# Arduino_and_PMOD_Connectors.net
KiCad netlist of a schematic drawn in Altium Designer
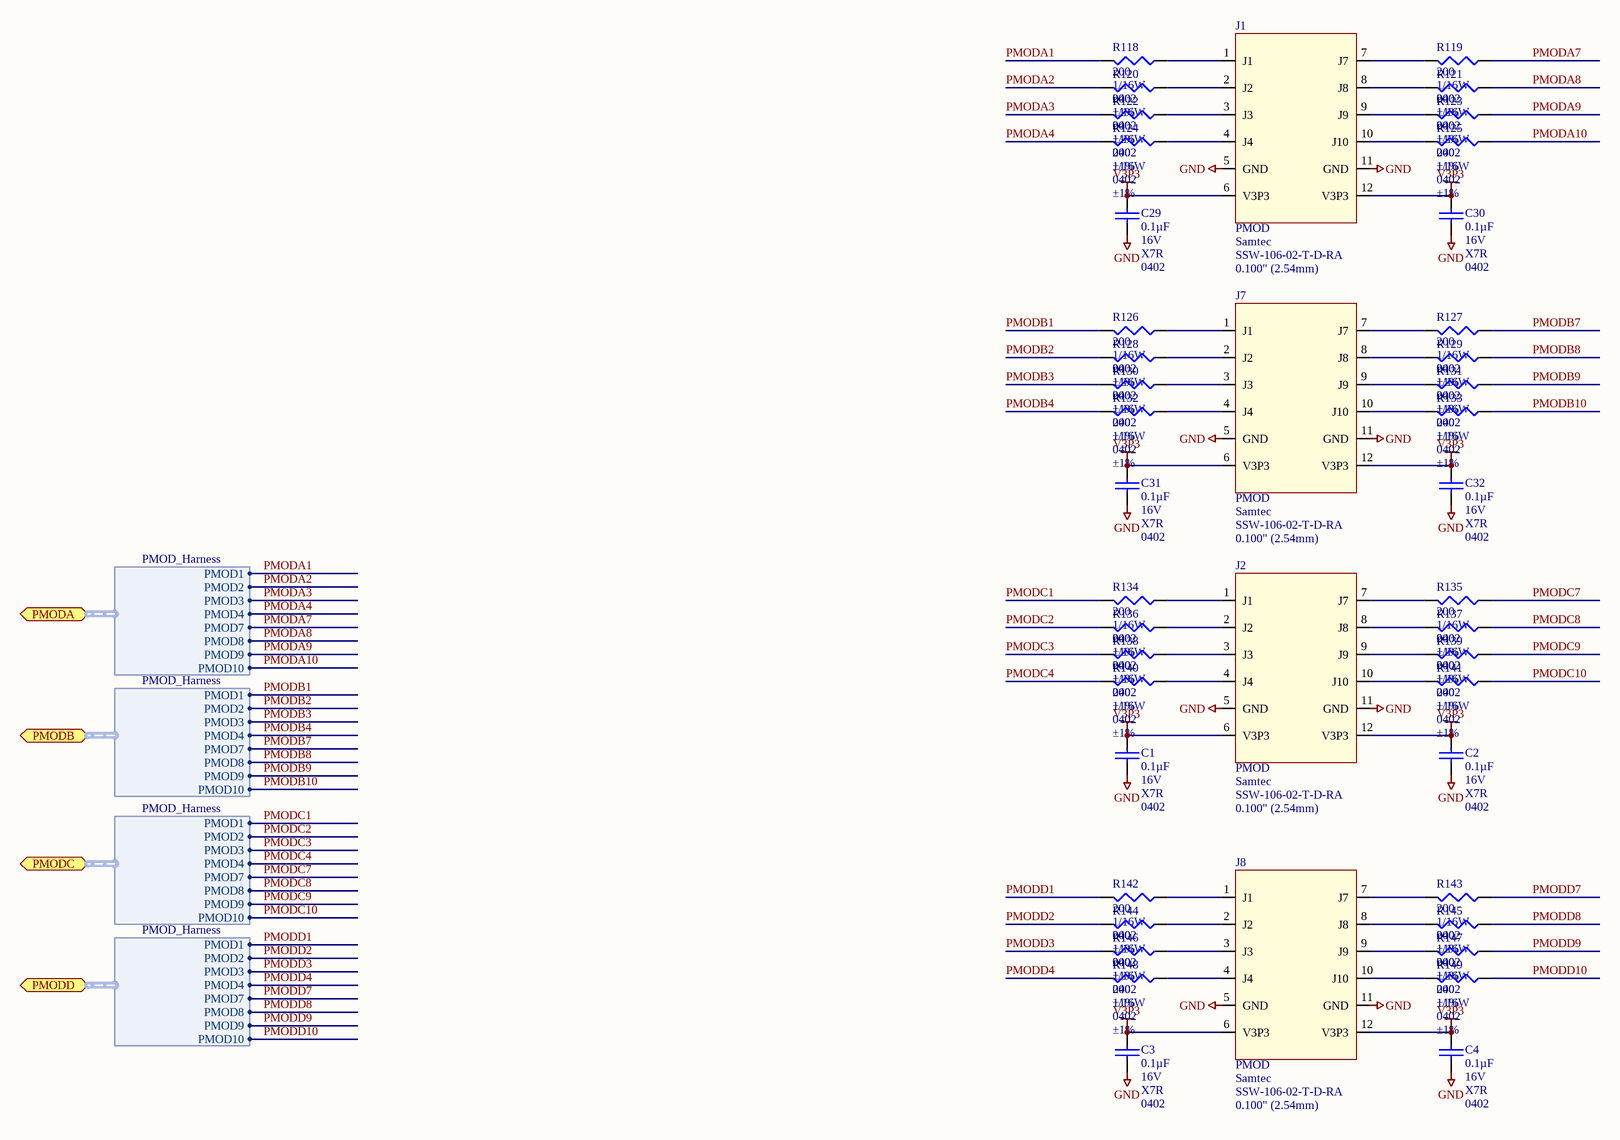
[diagram p0: Arduino and PMOD Connectors.SchDoc]

(export (version "E")
  (design (tool "Eeschema 10.0.6"))
  (components
    (comp (ref "C1")
      (value "0.1uF")
      (footprint "C_0402")
      (description "CAP CER .10UF 16V X7R 0402")
      (fields
        (field (name "MANUFACTURER") "Murata Electronics North America")
        (field (name "MANUFACTURER PART NUMBER") "GRM155R71C104KA88J")
        (field (name "CAPACITANCE") "0.1µF")
        (field (name "VOLTAGE - RATED") "16V")
        (field (name "TEMPERATURE COEFFICIENT") "X7R")
        (field (name "PACKAGE / CASE") "0402")
      )
      (libsource (lib "Main LibraryX") (part "C_0402_0.1UF_16V"))
    )
    (comp (ref "C2")
      (value "0.1uF")
      (footprint "C_0402")
      (description "CAP CER .10UF 16V X7R 0402")
      (fields
        (field (name "MANUFACTURER") "Murata Electronics North America")
        (field (name "MANUFACTURER PART NUMBER") "GRM155R71C104KA88J")
        (field (name "CAPACITANCE") "0.1µF")
        (field (name "VOLTAGE - RATED") "16V")
        (field (name "TEMPERATURE COEFFICIENT") "X7R")
        (field (name "PACKAGE / CASE") "0402")
      )
      (libsource (lib "Main LibraryX") (part "C_0402_0.1UF_16V"))
    )
    (comp (ref "C3")
      (value "0.1uF")
      (footprint "C_0402")
      (description "CAP CER .10UF 16V X7R 0402")
      (fields
        (field (name "MANUFACTURER") "Murata Electronics North America")
        (field (name "MANUFACTURER PART NUMBER") "GRM155R71C104KA88J")
        (field (name "CAPACITANCE") "0.1µF")
        (field (name "VOLTAGE - RATED") "16V")
        (field (name "TEMPERATURE COEFFICIENT") "X7R")
        (field (name "PACKAGE / CASE") "0402")
      )
      (libsource (lib "Main LibraryX") (part "C_0402_0.1UF_16V"))
    )
    (comp (ref "C4")
      (value "0.1uF")
      (footprint "C_0402")
      (description "CAP CER .10UF 16V X7R 0402")
      (fields
        (field (name "MANUFACTURER") "Murata Electronics North America")
        (field (name "MANUFACTURER PART NUMBER") "GRM155R71C104KA88J")
        (field (name "CAPACITANCE") "0.1µF")
        (field (name "VOLTAGE - RATED") "16V")
        (field (name "TEMPERATURE COEFFICIENT") "X7R")
        (field (name "PACKAGE / CASE") "0402")
      )
      (libsource (lib "Main LibraryX") (part "C_0402_0.1UF_16V"))
    )
    (comp (ref "C29")
      (value "0.1uF")
      (footprint "C_0402")
      (description "CAP CER .10UF 16V X7R 0402")
      (fields
        (field (name "MANUFACTURER") "Murata Electronics North America")
        (field (name "MANUFACTURER PART NUMBER") "GRM155R71C104KA88J")
        (field (name "CAPACITANCE") "0.1µF")
        (field (name "VOLTAGE - RATED") "16V")
        (field (name "TEMPERATURE COEFFICIENT") "X7R")
        (field (name "PACKAGE / CASE") "0402")
      )
      (libsource (lib "Main LibraryX") (part "C_0402_0.1UF_16V"))
    )
    (comp (ref "C30")
      (value "0.1uF")
      (footprint "C_0402")
      (description "CAP CER .10UF 16V X7R 0402")
      (fields
        (field (name "MANUFACTURER") "Murata Electronics North America")
        (field (name "MANUFACTURER PART NUMBER") "GRM155R71C104KA88J")
        (field (name "CAPACITANCE") "0.1µF")
        (field (name "VOLTAGE - RATED") "16V")
        (field (name "TEMPERATURE COEFFICIENT") "X7R")
        (field (name "PACKAGE / CASE") "0402")
      )
      (libsource (lib "Main LibraryX") (part "C_0402_0.1UF_16V"))
    )
    (comp (ref "C31")
      (value "0.1uF")
      (footprint "C_0402")
      (description "CAP CER .10UF 16V X7R 0402")
      (fields
        (field (name "MANUFACTURER") "Murata Electronics North America")
        (field (name "MANUFACTURER PART NUMBER") "GRM155R71C104KA88J")
        (field (name "CAPACITANCE") "0.1µF")
        (field (name "VOLTAGE - RATED") "16V")
        (field (name "TEMPERATURE COEFFICIENT") "X7R")
        (field (name "PACKAGE / CASE") "0402")
      )
      (libsource (lib "Main LibraryX") (part "C_0402_0.1UF_16V"))
    )
    (comp (ref "C32")
      (value "0.1uF")
      (footprint "C_0402")
      (description "CAP CER .10UF 16V X7R 0402")
      (fields
        (field (name "MANUFACTURER") "Murata Electronics North America")
        (field (name "MANUFACTURER PART NUMBER") "GRM155R71C104KA88J")
        (field (name "CAPACITANCE") "0.1µF")
        (field (name "VOLTAGE - RATED") "16V")
        (field (name "TEMPERATURE COEFFICIENT") "X7R")
        (field (name "PACKAGE / CASE") "0402")
      )
      (libsource (lib "Main LibraryX") (part "C_0402_0.1UF_16V"))
    )
    (comp (ref "J1")
      (value "PMOD")
      (footprint "PMOD")
      (description "CONN FEMALE 12POS DL .1\" R/A TIN")
      (fields
        (field (name "MANUFACTURER") "Samtec")
        (field (name "MANUFACTURER PART NUMBER") "SSW-106-02-T-D-RA")
        (field (name "PITCH") "0.100\" (2.54mm)")
      )
      (libsource (lib "Main LibraryX") (part "J_PMOD"))
    )
    (comp (ref "J2")
      (value "PMOD")
      (footprint "PMOD")
      (description "CONN FEMALE 12POS DL .1\" R/A TIN")
      (fields
        (field (name "MANUFACTURER") "Samtec")
        (field (name "MANUFACTURER PART NUMBER") "SSW-106-02-T-D-RA")
        (field (name "PITCH") "0.100\" (2.54mm)")
      )
      (libsource (lib "Main LibraryX") (part "J_PMOD"))
    )
    (comp (ref "J7")
      (value "PMOD")
      (footprint "PMOD")
      (description "CONN FEMALE 12POS DL .1\" R/A TIN")
      (fields
        (field (name "MANUFACTURER") "Samtec")
        (field (name "MANUFACTURER PART NUMBER") "SSW-106-02-T-D-RA")
        (field (name "PITCH") "0.100\" (2.54mm)")
      )
      (libsource (lib "Main LibraryX") (part "J_PMOD"))
    )
    (comp (ref "J8")
      (value "PMOD")
      (footprint "PMOD")
      (description "CONN FEMALE 12POS DL .1\" R/A TIN")
      (fields
        (field (name "MANUFACTURER") "Samtec")
        (field (name "MANUFACTURER PART NUMBER") "SSW-106-02-T-D-RA")
        (field (name "PITCH") "0.100\" (2.54mm)")
      )
      (libsource (lib "Main LibraryX") (part "J_PMOD"))
    )
    (comp (ref "R118")
      (value "R_0402_200")
      (footprint "R_0402")
      (description "RES 200 OHM 1/10W 1% 0402 SMD")
      (fields
        (field (name "MANUFACTURER") "Panasonic Electronic Components")
        (field (name "MANUFACTURER PART NUMBER") "ERJ-2RKF2000X")
        (field (name "RESISTANCE IN OHMS") "200")
        (field (name "POWER (WATTS)") "1/16W")
        (field (name "CASE") "0402")
        (field (name "TOLERANCE") "±1%")
      )
      (libsource (lib "Main LibraryX") (part "R_0402_200"))
    )
    (comp (ref "R119")
      (value "R_0402_200")
      (footprint "R_0402")
      (description "RES 200 OHM 1/10W 1% 0402 SMD")
      (fields
        (field (name "MANUFACTURER") "Panasonic Electronic Components")
        (field (name "MANUFACTURER PART NUMBER") "ERJ-2RKF2000X")
        (field (name "RESISTANCE IN OHMS") "200")
        (field (name "POWER (WATTS)") "1/16W")
        (field (name "CASE") "0402")
        (field (name "TOLERANCE") "±1%")
      )
      (libsource (lib "Main LibraryX") (part "R_0402_200"))
    )
    (comp (ref "R120")
      (value "R_0402_200")
      (footprint "R_0402")
      (description "RES 200 OHM 1/10W 1% 0402 SMD")
      (fields
        (field (name "MANUFACTURER") "Panasonic Electronic Components")
        (field (name "MANUFACTURER PART NUMBER") "ERJ-2RKF2000X")
        (field (name "RESISTANCE IN OHMS") "200")
        (field (name "POWER (WATTS)") "1/16W")
        (field (name "CASE") "0402")
        (field (name "TOLERANCE") "±1%")
      )
      (libsource (lib "Main LibraryX") (part "R_0402_200"))
    )
    (comp (ref "R121")
      (value "R_0402_200")
      (footprint "R_0402")
      (description "RES 200 OHM 1/10W 1% 0402 SMD")
      (fields
        (field (name "MANUFACTURER") "Panasonic Electronic Components")
        (field (name "MANUFACTURER PART NUMBER") "ERJ-2RKF2000X")
        (field (name "RESISTANCE IN OHMS") "200")
        (field (name "POWER (WATTS)") "1/16W")
        (field (name "CASE") "0402")
        (field (name "TOLERANCE") "±1%")
      )
      (libsource (lib "Main LibraryX") (part "R_0402_200"))
    )
    (comp (ref "R122")
      (value "R_0402_200")
      (footprint "R_0402")
      (description "RES 200 OHM 1/10W 1% 0402 SMD")
      (fields
        (field (name "MANUFACTURER") "Panasonic Electronic Components")
        (field (name "MANUFACTURER PART NUMBER") "ERJ-2RKF2000X")
        (field (name "RESISTANCE IN OHMS") "200")
        (field (name "POWER (WATTS)") "1/16W")
        (field (name "CASE") "0402")
        (field (name "TOLERANCE") "±1%")
      )
      (libsource (lib "Main LibraryX") (part "R_0402_200"))
    )
    (comp (ref "R123")
      (value "R_0402_200")
      (footprint "R_0402")
      (description "RES 200 OHM 1/10W 1% 0402 SMD")
      (fields
        (field (name "MANUFACTURER") "Panasonic Electronic Components")
        (field (name "MANUFACTURER PART NUMBER") "ERJ-2RKF2000X")
        (field (name "RESISTANCE IN OHMS") "200")
        (field (name "POWER (WATTS)") "1/16W")
        (field (name "CASE") "0402")
        (field (name "TOLERANCE") "±1%")
      )
      (libsource (lib "Main LibraryX") (part "R_0402_200"))
    )
    (comp (ref "R124")
      (value "R_0402_200")
      (footprint "R_0402")
      (description "RES 200 OHM 1/10W 1% 0402 SMD")
      (fields
        (field (name "MANUFACTURER") "Panasonic Electronic Components")
        (field (name "MANUFACTURER PART NUMBER") "ERJ-2RKF2000X")
        (field (name "RESISTANCE IN OHMS") "200")
        (field (name "POWER (WATTS)") "1/16W")
        (field (name "CASE") "0402")
        (field (name "TOLERANCE") "±1%")
      )
      (libsource (lib "Main LibraryX") (part "R_0402_200"))
    )
    (comp (ref "R125")
      (value "R_0402_200")
      (footprint "R_0402")
      (description "RES 200 OHM 1/10W 1% 0402 SMD")
      (fields
        (field (name "MANUFACTURER") "Panasonic Electronic Components")
        (field (name "MANUFACTURER PART NUMBER") "ERJ-2RKF2000X")
        (field (name "RESISTANCE IN OHMS") "200")
        (field (name "POWER (WATTS)") "1/16W")
        (field (name "CASE") "0402")
        (field (name "TOLERANCE") "±1%")
      )
      (libsource (lib "Main LibraryX") (part "R_0402_200"))
    )
    (comp (ref "R126")
      (value "R_0402_200")
      (footprint "R_0402")
      (description "RES 200 OHM 1/10W 1% 0402 SMD")
      (fields
        (field (name "MANUFACTURER") "Panasonic Electronic Components")
        (field (name "MANUFACTURER PART NUMBER") "ERJ-2RKF2000X")
        (field (name "RESISTANCE IN OHMS") "200")
        (field (name "POWER (WATTS)") "1/16W")
        (field (name "CASE") "0402")
        (field (name "TOLERANCE") "±1%")
      )
      (libsource (lib "Main LibraryX") (part "R_0402_200"))
    )
    (comp (ref "R127")
      (value "R_0402_200")
      (footprint "R_0402")
      (description "RES 200 OHM 1/10W 1% 0402 SMD")
      (fields
        (field (name "MANUFACTURER") "Panasonic Electronic Components")
        (field (name "MANUFACTURER PART NUMBER") "ERJ-2RKF2000X")
        (field (name "RESISTANCE IN OHMS") "200")
        (field (name "POWER (WATTS)") "1/16W")
        (field (name "CASE") "0402")
        (field (name "TOLERANCE") "±1%")
      )
      (libsource (lib "Main LibraryX") (part "R_0402_200"))
    )
    (comp (ref "R128")
      (value "R_0402_200")
      (footprint "R_0402")
      (description "RES 200 OHM 1/10W 1% 0402 SMD")
      (fields
        (field (name "MANUFACTURER") "Panasonic Electronic Components")
        (field (name "MANUFACTURER PART NUMBER") "ERJ-2RKF2000X")
        (field (name "RESISTANCE IN OHMS") "200")
        (field (name "POWER (WATTS)") "1/16W")
        (field (name "CASE") "0402")
        (field (name "TOLERANCE") "±1%")
      )
      (libsource (lib "Main LibraryX") (part "R_0402_200"))
    )
    (comp (ref "R129")
      (value "R_0402_200")
      (footprint "R_0402")
      (description "RES 200 OHM 1/10W 1% 0402 SMD")
      (fields
        (field (name "MANUFACTURER") "Panasonic Electronic Components")
        (field (name "MANUFACTURER PART NUMBER") "ERJ-2RKF2000X")
        (field (name "RESISTANCE IN OHMS") "200")
        (field (name "POWER (WATTS)") "1/16W")
        (field (name "CASE") "0402")
        (field (name "TOLERANCE") "±1%")
      )
      (libsource (lib "Main LibraryX") (part "R_0402_200"))
    )
    (comp (ref "R130")
      (value "R_0402_200")
      (footprint "R_0402")
      (description "RES 200 OHM 1/10W 1% 0402 SMD")
      (fields
        (field (name "MANUFACTURER") "Panasonic Electronic Components")
        (field (name "MANUFACTURER PART NUMBER") "ERJ-2RKF2000X")
        (field (name "RESISTANCE IN OHMS") "200")
        (field (name "POWER (WATTS)") "1/16W")
        (field (name "CASE") "0402")
        (field (name "TOLERANCE") "±1%")
      )
      (libsource (lib "Main LibraryX") (part "R_0402_200"))
    )
    (comp (ref "R131")
      (value "R_0402_200")
      (footprint "R_0402")
      (description "RES 200 OHM 1/10W 1% 0402 SMD")
      (fields
        (field (name "MANUFACTURER") "Panasonic Electronic Components")
        (field (name "MANUFACTURER PART NUMBER") "ERJ-2RKF2000X")
        (field (name "RESISTANCE IN OHMS") "200")
        (field (name "POWER (WATTS)") "1/16W")
        (field (name "CASE") "0402")
        (field (name "TOLERANCE") "±1%")
      )
      (libsource (lib "Main LibraryX") (part "R_0402_200"))
    )
    (comp (ref "R132")
      (value "R_0402_200")
      (footprint "R_0402")
      (description "RES 200 OHM 1/10W 1% 0402 SMD")
      (fields
        (field (name "MANUFACTURER") "Panasonic Electronic Components")
        (field (name "MANUFACTURER PART NUMBER") "ERJ-2RKF2000X")
        (field (name "RESISTANCE IN OHMS") "200")
        (field (name "POWER (WATTS)") "1/16W")
        (field (name "CASE") "0402")
        (field (name "TOLERANCE") "±1%")
      )
      (libsource (lib "Main LibraryX") (part "R_0402_200"))
    )
    (comp (ref "R133")
      (value "R_0402_200")
      (footprint "R_0402")
      (description "RES 200 OHM 1/10W 1% 0402 SMD")
      (fields
        (field (name "MANUFACTURER") "Panasonic Electronic Components")
        (field (name "MANUFACTURER PART NUMBER") "ERJ-2RKF2000X")
        (field (name "RESISTANCE IN OHMS") "200")
        (field (name "POWER (WATTS)") "1/16W")
        (field (name "CASE") "0402")
        (field (name "TOLERANCE") "±1%")
      )
      (libsource (lib "Main LibraryX") (part "R_0402_200"))
    )
    (comp (ref "R134")
      (value "R_0402_200")
      (footprint "R_0402")
      (description "RES 200 OHM 1/10W 1% 0402 SMD")
      (fields
        (field (name "MANUFACTURER") "Panasonic Electronic Components")
        (field (name "MANUFACTURER PART NUMBER") "ERJ-2RKF2000X")
        (field (name "RESISTANCE IN OHMS") "200")
        (field (name "POWER (WATTS)") "1/16W")
        (field (name "CASE") "0402")
        (field (name "TOLERANCE") "±1%")
      )
      (libsource (lib "Main LibraryX") (part "R_0402_200"))
    )
    (comp (ref "R135")
      (value "R_0402_200")
      (footprint "R_0402")
      (description "RES 200 OHM 1/10W 1% 0402 SMD")
      (fields
        (field (name "MANUFACTURER") "Panasonic Electronic Components")
        (field (name "MANUFACTURER PART NUMBER") "ERJ-2RKF2000X")
        (field (name "RESISTANCE IN OHMS") "200")
        (field (name "POWER (WATTS)") "1/16W")
        (field (name "CASE") "0402")
        (field (name "TOLERANCE") "±1%")
      )
      (libsource (lib "Main LibraryX") (part "R_0402_200"))
    )
    (comp (ref "R136")
      (value "R_0402_200")
      (footprint "R_0402")
      (description "RES 200 OHM 1/10W 1% 0402 SMD")
      (fields
        (field (name "MANUFACTURER") "Panasonic Electronic Components")
        (field (name "MANUFACTURER PART NUMBER") "ERJ-2RKF2000X")
        (field (name "RESISTANCE IN OHMS") "200")
        (field (name "POWER (WATTS)") "1/16W")
        (field (name "CASE") "0402")
        (field (name "TOLERANCE") "±1%")
      )
      (libsource (lib "Main LibraryX") (part "R_0402_200"))
    )
    (comp (ref "R137")
      (value "R_0402_200")
      (footprint "R_0402")
      (description "RES 200 OHM 1/10W 1% 0402 SMD")
      (fields
        (field (name "MANUFACTURER") "Panasonic Electronic Components")
        (field (name "MANUFACTURER PART NUMBER") "ERJ-2RKF2000X")
        (field (name "RESISTANCE IN OHMS") "200")
        (field (name "POWER (WATTS)") "1/16W")
        (field (name "CASE") "0402")
        (field (name "TOLERANCE") "±1%")
      )
      (libsource (lib "Main LibraryX") (part "R_0402_200"))
    )
    (comp (ref "R138")
      (value "R_0402_200")
      (footprint "R_0402")
      (description "RES 200 OHM 1/10W 1% 0402 SMD")
      (fields
        (field (name "MANUFACTURER") "Panasonic Electronic Components")
        (field (name "MANUFACTURER PART NUMBER") "ERJ-2RKF2000X")
        (field (name "RESISTANCE IN OHMS") "200")
        (field (name "POWER (WATTS)") "1/16W")
        (field (name "CASE") "0402")
        (field (name "TOLERANCE") "±1%")
      )
      (libsource (lib "Main LibraryX") (part "R_0402_200"))
    )
    (comp (ref "R139")
      (value "R_0402_200")
      (footprint "R_0402")
      (description "RES 200 OHM 1/10W 1% 0402 SMD")
      (fields
        (field (name "MANUFACTURER") "Panasonic Electronic Components")
        (field (name "MANUFACTURER PART NUMBER") "ERJ-2RKF2000X")
        (field (name "RESISTANCE IN OHMS") "200")
        (field (name "POWER (WATTS)") "1/16W")
        (field (name "CASE") "0402")
        (field (name "TOLERANCE") "±1%")
      )
      (libsource (lib "Main LibraryX") (part "R_0402_200"))
    )
    (comp (ref "R140")
      (value "R_0402_200")
      (footprint "R_0402")
      (description "RES 200 OHM 1/10W 1% 0402 SMD")
      (fields
        (field (name "MANUFACTURER") "Panasonic Electronic Components")
        (field (name "MANUFACTURER PART NUMBER") "ERJ-2RKF2000X")
        (field (name "RESISTANCE IN OHMS") "200")
        (field (name "POWER (WATTS)") "1/16W")
        (field (name "CASE") "0402")
        (field (name "TOLERANCE") "±1%")
      )
      (libsource (lib "Main LibraryX") (part "R_0402_200"))
    )
    (comp (ref "R141")
      (value "R_0402_200")
      (footprint "R_0402")
      (description "RES 200 OHM 1/10W 1% 0402 SMD")
      (fields
        (field (name "MANUFACTURER") "Panasonic Electronic Components")
        (field (name "MANUFACTURER PART NUMBER") "ERJ-2RKF2000X")
        (field (name "RESISTANCE IN OHMS") "200")
        (field (name "POWER (WATTS)") "1/16W")
        (field (name "CASE") "0402")
        (field (name "TOLERANCE") "±1%")
      )
      (libsource (lib "Main LibraryX") (part "R_0402_200"))
    )
    (comp (ref "R142")
      (value "R_0402_200")
      (footprint "R_0402")
      (description "RES 200 OHM 1/10W 1% 0402 SMD")
      (fields
        (field (name "MANUFACTURER") "Panasonic Electronic Components")
        (field (name "MANUFACTURER PART NUMBER") "ERJ-2RKF2000X")
        (field (name "RESISTANCE IN OHMS") "200")
        (field (name "POWER (WATTS)") "1/16W")
        (field (name "CASE") "0402")
        (field (name "TOLERANCE") "±1%")
      )
      (libsource (lib "Main LibraryX") (part "R_0402_200"))
    )
    (comp (ref "R143")
      (value "R_0402_200")
      (footprint "R_0402")
      (description "RES 200 OHM 1/10W 1% 0402 SMD")
      (fields
        (field (name "MANUFACTURER") "Panasonic Electronic Components")
        (field (name "MANUFACTURER PART NUMBER") "ERJ-2RKF2000X")
        (field (name "RESISTANCE IN OHMS") "200")
        (field (name "POWER (WATTS)") "1/16W")
        (field (name "CASE") "0402")
        (field (name "TOLERANCE") "±1%")
      )
      (libsource (lib "Main LibraryX") (part "R_0402_200"))
    )
    (comp (ref "R144")
      (value "R_0402_200")
      (footprint "R_0402")
      (description "RES 200 OHM 1/10W 1% 0402 SMD")
      (fields
        (field (name "MANUFACTURER") "Panasonic Electronic Components")
        (field (name "MANUFACTURER PART NUMBER") "ERJ-2RKF2000X")
        (field (name "RESISTANCE IN OHMS") "200")
        (field (name "POWER (WATTS)") "1/16W")
        (field (name "CASE") "0402")
        (field (name "TOLERANCE") "±1%")
      )
      (libsource (lib "Main LibraryX") (part "R_0402_200"))
    )
    (comp (ref "R145")
      (value "R_0402_200")
      (footprint "R_0402")
      (description "RES 200 OHM 1/10W 1% 0402 SMD")
      (fields
        (field (name "MANUFACTURER") "Panasonic Electronic Components")
        (field (name "MANUFACTURER PART NUMBER") "ERJ-2RKF2000X")
        (field (name "RESISTANCE IN OHMS") "200")
        (field (name "POWER (WATTS)") "1/16W")
        (field (name "CASE") "0402")
        (field (name "TOLERANCE") "±1%")
      )
      (libsource (lib "Main LibraryX") (part "R_0402_200"))
    )
    (comp (ref "R146")
      (value "R_0402_200")
      (footprint "R_0402")
      (description "RES 200 OHM 1/10W 1% 0402 SMD")
      (fields
        (field (name "MANUFACTURER") "Panasonic Electronic Components")
        (field (name "MANUFACTURER PART NUMBER") "ERJ-2RKF2000X")
        (field (name "RESISTANCE IN OHMS") "200")
        (field (name "POWER (WATTS)") "1/16W")
        (field (name "CASE") "0402")
        (field (name "TOLERANCE") "±1%")
      )
      (libsource (lib "Main LibraryX") (part "R_0402_200"))
    )
    (comp (ref "R147")
      (value "R_0402_200")
      (footprint "R_0402")
      (description "RES 200 OHM 1/10W 1% 0402 SMD")
      (fields
        (field (name "MANUFACTURER") "Panasonic Electronic Components")
        (field (name "MANUFACTURER PART NUMBER") "ERJ-2RKF2000X")
        (field (name "RESISTANCE IN OHMS") "200")
        (field (name "POWER (WATTS)") "1/16W")
        (field (name "CASE") "0402")
        (field (name "TOLERANCE") "±1%")
      )
      (libsource (lib "Main LibraryX") (part "R_0402_200"))
    )
    (comp (ref "R148")
      (value "R_0402_200")
      (footprint "R_0402")
      (description "RES 200 OHM 1/10W 1% 0402 SMD")
      (fields
        (field (name "MANUFACTURER") "Panasonic Electronic Components")
        (field (name "MANUFACTURER PART NUMBER") "ERJ-2RKF2000X")
        (field (name "RESISTANCE IN OHMS") "200")
        (field (name "POWER (WATTS)") "1/16W")
        (field (name "CASE") "0402")
        (field (name "TOLERANCE") "±1%")
      )
      (libsource (lib "Main LibraryX") (part "R_0402_200"))
    )
    (comp (ref "R149")
      (value "R_0402_200")
      (footprint "R_0402")
      (description "RES 200 OHM 1/10W 1% 0402 SMD")
      (fields
        (field (name "MANUFACTURER") "Panasonic Electronic Components")
        (field (name "MANUFACTURER PART NUMBER") "ERJ-2RKF2000X")
        (field (name "RESISTANCE IN OHMS") "200")
        (field (name "POWER (WATTS)") "1/16W")
        (field (name "CASE") "0402")
        (field (name "TOLERANCE") "±1%")
      )
      (libsource (lib "Main LibraryX") (part "R_0402_200"))
    )
  )
  (nets
    (net (code "2") (name "/PMODA1") (class "Default")
      (node (ref "R118") (pin "1") (pinfunction "1_1") (pintype "passive"))
    )
    (net (code "3") (name "/PMODA2") (class "Default")
      (node (ref "R120") (pin "1") (pinfunction "1_1") (pintype "passive"))
    )
    (net (code "4") (name "/PMODA3") (class "Default")
      (node (ref "R122") (pin "1") (pinfunction "1_1") (pintype "passive"))
    )
    (net (code "5") (name "/PMODA4") (class "Default")
      (node (ref "R124") (pin "1") (pinfunction "1_1") (pintype "passive"))
    )
    (net (code "6") (name "/PMODA7") (class "Default")
      (node (ref "R119") (pin "2") (pinfunction "2_2") (pintype "passive"))
    )
    (net (code "7") (name "/PMODA8") (class "Default")
      (node (ref "R121") (pin "2") (pinfunction "2_2") (pintype "passive"))
    )
    (net (code "8") (name "/PMODA9") (class "Default")
      (node (ref "R123") (pin "2") (pinfunction "2_2") (pintype "passive"))
    )
    (net (code "9") (name "/PMODA10") (class "Default")
      (node (ref "R125") (pin "2") (pinfunction "2_2") (pintype "passive"))
    )
    (net (code "10") (name "/PMODB1") (class "Default")
      (node (ref "R126") (pin "1") (pinfunction "1_1") (pintype "passive"))
    )
    (net (code "11") (name "/PMODB2") (class "Default")
      (node (ref "R128") (pin "1") (pinfunction "1_1") (pintype "passive"))
    )
    (net (code "12") (name "/PMODB3") (class "Default")
      (node (ref "R130") (pin "1") (pinfunction "1_1") (pintype "passive"))
    )
    (net (code "13") (name "/PMODB4") (class "Default")
      (node (ref "R132") (pin "1") (pinfunction "1_1") (pintype "passive"))
    )
    (net (code "14") (name "/PMODB7") (class "Default")
      (node (ref "R127") (pin "2") (pinfunction "2_2") (pintype "passive"))
    )
    (net (code "15") (name "/PMODB8") (class "Default")
      (node (ref "R129") (pin "2") (pinfunction "2_2") (pintype "passive"))
    )
    (net (code "16") (name "/PMODB9") (class "Default")
      (node (ref "R131") (pin "2") (pinfunction "2_2") (pintype "passive"))
    )
    (net (code "17") (name "/PMODB10") (class "Default")
      (node (ref "R133") (pin "2") (pinfunction "2_2") (pintype "passive"))
    )
    (net (code "18") (name "/PMODC1") (class "Default")
      (node (ref "R134") (pin "1") (pinfunction "1_1") (pintype "passive"))
    )
    (net (code "19") (name "/PMODC2") (class "Default")
      (node (ref "R136") (pin "1") (pinfunction "1_1") (pintype "passive"))
    )
    (net (code "20") (name "/PMODC3") (class "Default")
      (node (ref "R138") (pin "1") (pinfunction "1_1") (pintype "passive"))
    )
    (net (code "21") (name "/PMODC4") (class "Default")
      (node (ref "R140") (pin "1") (pinfunction "1_1") (pintype "passive"))
    )
    (net (code "22") (name "/PMODC7") (class "Default")
      (node (ref "R135") (pin "2") (pinfunction "2_2") (pintype "passive"))
    )
    (net (code "23") (name "/PMODC8") (class "Default")
      (node (ref "R137") (pin "2") (pinfunction "2_2") (pintype "passive"))
    )
    (net (code "24") (name "/PMODC9") (class "Default")
      (node (ref "R139") (pin "2") (pinfunction "2_2") (pintype "passive"))
    )
    (net (code "25") (name "/PMODC10") (class "Default")
      (node (ref "R141") (pin "2") (pinfunction "2_2") (pintype "passive"))
    )
    (net (code "26") (name "/PMODD1") (class "Default")
      (node (ref "R142") (pin "1") (pinfunction "1_1") (pintype "passive"))
    )
    (net (code "27") (name "/PMODD2") (class "Default")
      (node (ref "R144") (pin "1") (pinfunction "1_1") (pintype "passive"))
    )
    (net (code "28") (name "/PMODD3") (class "Default")
      (node (ref "R146") (pin "1") (pinfunction "1_1") (pintype "passive"))
    )
    (net (code "29") (name "/PMODD4") (class "Default")
      (node (ref "R148") (pin "1") (pinfunction "1_1") (pintype "passive"))
    )
    (net (code "30") (name "/PMODD7") (class "Default")
      (node (ref "R143") (pin "2") (pinfunction "2_2") (pintype "passive"))
    )
    (net (code "31") (name "/PMODD8") (class "Default")
      (node (ref "R145") (pin "2") (pinfunction "2_2") (pintype "passive"))
    )
    (net (code "32") (name "/PMODD9") (class "Default")
      (node (ref "R147") (pin "2") (pinfunction "2_2") (pintype "passive"))
    )
    (net (code "33") (name "/PMODD10") (class "Default")
      (node (ref "R149") (pin "2") (pinfunction "2_2") (pintype "passive"))
    )
    (net (code "35") (name "GND") (class "Default")
      (node (ref "C1") (pin "1") (pinfunction "1_1") (pintype "passive"))
      (node (ref "C2") (pin "1") (pinfunction "1_1") (pintype "passive"))
      (node (ref "C29") (pin "1") (pinfunction "1_1") (pintype "passive"))
      (node (ref "C3") (pin "1") (pinfunction "1_1") (pintype "passive"))
      (node (ref "C30") (pin "1") (pinfunction "1_1") (pintype "passive"))
      (node (ref "C31") (pin "1") (pinfunction "1_1") (pintype "passive"))
      (node (ref "C32") (pin "1") (pinfunction "1_1") (pintype "passive"))
      (node (ref "C4") (pin "1") (pinfunction "1_1") (pintype "passive"))
      (node (ref "J1") (pin "11") (pinfunction "GND_11") (pintype "passive"))
      (node (ref "J1") (pin "5") (pinfunction "GND_5") (pintype "passive"))
      (node (ref "J2") (pin "11") (pinfunction "GND_11") (pintype "passive"))
      (node (ref "J2") (pin "5") (pinfunction "GND_5") (pintype "passive"))
      (node (ref "J7") (pin "11") (pinfunction "GND_11") (pintype "passive"))
      (node (ref "J7") (pin "5") (pinfunction "GND_5") (pintype "passive"))
      (node (ref "J8") (pin "11") (pinfunction "GND_11") (pintype "passive"))
      (node (ref "J8") (pin "5") (pinfunction "GND_5") (pintype "passive"))
    )
    (net (code "36") (name "Net-(J1-J1)") (class "Default")
      (node (ref "J1") (pin "1") (pinfunction "J1_1") (pintype "passive"))
      (node (ref "R118") (pin "2") (pinfunction "2_2") (pintype "passive"))
    )
    (net (code "37") (name "Net-(J1-J2)") (class "Default")
      (node (ref "J1") (pin "2") (pinfunction "J2_2") (pintype "passive"))
      (node (ref "R120") (pin "2") (pinfunction "2_2") (pintype "passive"))
    )
    (net (code "38") (name "Net-(J1-J3)") (class "Default")
      (node (ref "J1") (pin "3") (pinfunction "J3_3") (pintype "passive"))
      (node (ref "R122") (pin "2") (pinfunction "2_2") (pintype "passive"))
    )
    (net (code "39") (name "Net-(J1-J4)") (class "Default")
      (node (ref "J1") (pin "4") (pinfunction "J4_4") (pintype "passive"))
      (node (ref "R124") (pin "2") (pinfunction "2_2") (pintype "passive"))
    )
    (net (code "40") (name "Net-(J1-J7)") (class "Default")
      (node (ref "J1") (pin "7") (pinfunction "J7_7") (pintype "passive"))
      (node (ref "R119") (pin "1") (pinfunction "1_1") (pintype "passive"))
    )
    (net (code "41") (name "Net-(J1-J8)") (class "Default")
      (node (ref "J1") (pin "8") (pinfunction "J8_8") (pintype "passive"))
      (node (ref "R121") (pin "1") (pinfunction "1_1") (pintype "passive"))
    )
    (net (code "42") (name "Net-(J1-J9)") (class "Default")
      (node (ref "J1") (pin "9") (pinfunction "J9_9") (pintype "passive"))
      (node (ref "R123") (pin "1") (pinfunction "1_1") (pintype "passive"))
    )
    (net (code "43") (name "Net-(J1-J10)") (class "Default")
      (node (ref "J1") (pin "10") (pinfunction "J10_10") (pintype "passive"))
      (node (ref "R125") (pin "1") (pinfunction "1_1") (pintype "passive"))
    )
    (net (code "44") (name "Net-(J2-J1)") (class "Default")
      (node (ref "J2") (pin "1") (pinfunction "J1_1") (pintype "passive"))
      (node (ref "R134") (pin "2") (pinfunction "2_2") (pintype "passive"))
    )
    (net (code "45") (name "Net-(J2-J2)") (class "Default")
      (node (ref "J2") (pin "2") (pinfunction "J2_2") (pintype "passive"))
      (node (ref "R136") (pin "2") (pinfunction "2_2") (pintype "passive"))
    )
    (net (code "46") (name "Net-(J2-J3)") (class "Default")
      (node (ref "J2") (pin "3") (pinfunction "J3_3") (pintype "passive"))
      (node (ref "R138") (pin "2") (pinfunction "2_2") (pintype "passive"))
    )
    (net (code "47") (name "Net-(J2-J4)") (class "Default")
      (node (ref "J2") (pin "4") (pinfunction "J4_4") (pintype "passive"))
      (node (ref "R140") (pin "2") (pinfunction "2_2") (pintype "passive"))
    )
    (net (code "48") (name "Net-(J2-J7)") (class "Default")
      (node (ref "J2") (pin "7") (pinfunction "J7_7") (pintype "passive"))
      (node (ref "R135") (pin "1") (pinfunction "1_1") (pintype "passive"))
    )
    (net (code "49") (name "Net-(J2-J8)") (class "Default")
      (node (ref "J2") (pin "8") (pinfunction "J8_8") (pintype "passive"))
      (node (ref "R137") (pin "1") (pinfunction "1_1") (pintype "passive"))
    )
    (net (code "50") (name "Net-(J2-J9)") (class "Default")
      (node (ref "J2") (pin "9") (pinfunction "J9_9") (pintype "passive"))
      (node (ref "R139") (pin "1") (pinfunction "1_1") (pintype "passive"))
    )
    (net (code "51") (name "Net-(J2-J10)") (class "Default")
      (node (ref "J2") (pin "10") (pinfunction "J10_10") (pintype "passive"))
      (node (ref "R141") (pin "1") (pinfunction "1_1") (pintype "passive"))
    )
    (net (code "52") (name "Net-(J7-J1)") (class "Default")
      (node (ref "J7") (pin "1") (pinfunction "J1_1") (pintype "passive"))
      (node (ref "R126") (pin "2") (pinfunction "2_2") (pintype "passive"))
    )
    (net (code "53") (name "Net-(J7-J2)") (class "Default")
      (node (ref "J7") (pin "2") (pinfunction "J2_2") (pintype "passive"))
      (node (ref "R128") (pin "2") (pinfunction "2_2") (pintype "passive"))
    )
    (net (code "54") (name "Net-(J7-J3)") (class "Default")
      (node (ref "J7") (pin "3") (pinfunction "J3_3") (pintype "passive"))
      (node (ref "R130") (pin "2") (pinfunction "2_2") (pintype "passive"))
    )
    (net (code "55") (name "Net-(J7-J4)") (class "Default")
      (node (ref "J7") (pin "4") (pinfunction "J4_4") (pintype "passive"))
      (node (ref "R132") (pin "2") (pinfunction "2_2") (pintype "passive"))
    )
    (net (code "56") (name "Net-(J7-J7)") (class "Default")
      (node (ref "J7") (pin "7") (pinfunction "J7_7") (pintype "passive"))
      (node (ref "R127") (pin "1") (pinfunction "1_1") (pintype "passive"))
    )
    (net (code "57") (name "Net-(J7-J8)") (class "Default")
      (node (ref "J7") (pin "8") (pinfunction "J8_8") (pintype "passive"))
      (node (ref "R129") (pin "1") (pinfunction "1_1") (pintype "passive"))
    )
    (net (code "58") (name "Net-(J7-J9)") (class "Default")
      (node (ref "J7") (pin "9") (pinfunction "J9_9") (pintype "passive"))
      (node (ref "R131") (pin "1") (pinfunction "1_1") (pintype "passive"))
    )
    (net (code "59") (name "Net-(J7-J10)") (class "Default")
      (node (ref "J7") (pin "10") (pinfunction "J10_10") (pintype "passive"))
      (node (ref "R133") (pin "1") (pinfunction "1_1") (pintype "passive"))
    )
    (net (code "60") (name "Net-(J8-J1)") (class "Default")
      (node (ref "J8") (pin "1") (pinfunction "J1_1") (pintype "passive"))
      (node (ref "R142") (pin "2") (pinfunction "2_2") (pintype "passive"))
    )
    (net (code "61") (name "Net-(J8-J2)") (class "Default")
      (node (ref "J8") (pin "2") (pinfunction "J2_2") (pintype "passive"))
      (node (ref "R144") (pin "2") (pinfunction "2_2") (pintype "passive"))
    )
    (net (code "62") (name "Net-(J8-J3)") (class "Default")
      (node (ref "J8") (pin "3") (pinfunction "J3_3") (pintype "passive"))
      (node (ref "R146") (pin "2") (pinfunction "2_2") (pintype "passive"))
    )
    (net (code "63") (name "Net-(J8-J4)") (class "Default")
      (node (ref "J8") (pin "4") (pinfunction "J4_4") (pintype "passive"))
      (node (ref "R148") (pin "2") (pinfunction "2_2") (pintype "passive"))
    )
    (net (code "64") (name "Net-(J8-J7)") (class "Default")
      (node (ref "J8") (pin "7") (pinfunction "J7_7") (pintype "passive"))
      (node (ref "R143") (pin "1") (pinfunction "1_1") (pintype "passive"))
    )
    (net (code "65") (name "Net-(J8-J8)") (class "Default")
      (node (ref "J8") (pin "8") (pinfunction "J8_8") (pintype "passive"))
      (node (ref "R145") (pin "1") (pinfunction "1_1") (pintype "passive"))
    )
    (net (code "66") (name "Net-(J8-J9)") (class "Default")
      (node (ref "J8") (pin "9") (pinfunction "J9_9") (pintype "passive"))
      (node (ref "R147") (pin "1") (pinfunction "1_1") (pintype "passive"))
    )
    (net (code "67") (name "Net-(J8-J10)") (class "Default")
      (node (ref "J8") (pin "10") (pinfunction "J10_10") (pintype "passive"))
      (node (ref "R149") (pin "1") (pinfunction "1_1") (pintype "passive"))
    )
    (net (code "68") (name "V3P3") (class "Default")
      (node (ref "C1") (pin "2") (pinfunction "2_2") (pintype "passive"))
      (node (ref "C2") (pin "2") (pinfunction "2_2") (pintype "passive"))
      (node (ref "C29") (pin "2") (pinfunction "2_2") (pintype "passive"))
      (node (ref "C3") (pin "2") (pinfunction "2_2") (pintype "passive"))
      (node (ref "C30") (pin "2") (pinfunction "2_2") (pintype "passive"))
      (node (ref "C31") (pin "2") (pinfunction "2_2") (pintype "passive"))
      (node (ref "C32") (pin "2") (pinfunction "2_2") (pintype "passive"))
      (node (ref "C4") (pin "2") (pinfunction "2_2") (pintype "passive"))
      (node (ref "J1") (pin "12") (pinfunction "V3P3_12") (pintype "passive"))
      (node (ref "J1") (pin "6") (pinfunction "V3P3_6") (pintype "passive"))
      (node (ref "J2") (pin "12") (pinfunction "V3P3_12") (pintype "passive"))
      (node (ref "J2") (pin "6") (pinfunction "V3P3_6") (pintype "passive"))
      (node (ref "J7") (pin "12") (pinfunction "V3P3_12") (pintype "passive"))
      (node (ref "J7") (pin "6") (pinfunction "V3P3_6") (pintype "passive"))
      (node (ref "J8") (pin "12") (pinfunction "V3P3_12") (pintype "passive"))
      (node (ref "J8") (pin "6") (pinfunction "V3P3_6") (pintype "passive"))
    )
  )
)
